# ESP32V1_based_led_button.net
KiCad netlist of a schematic drawn in EAGLE
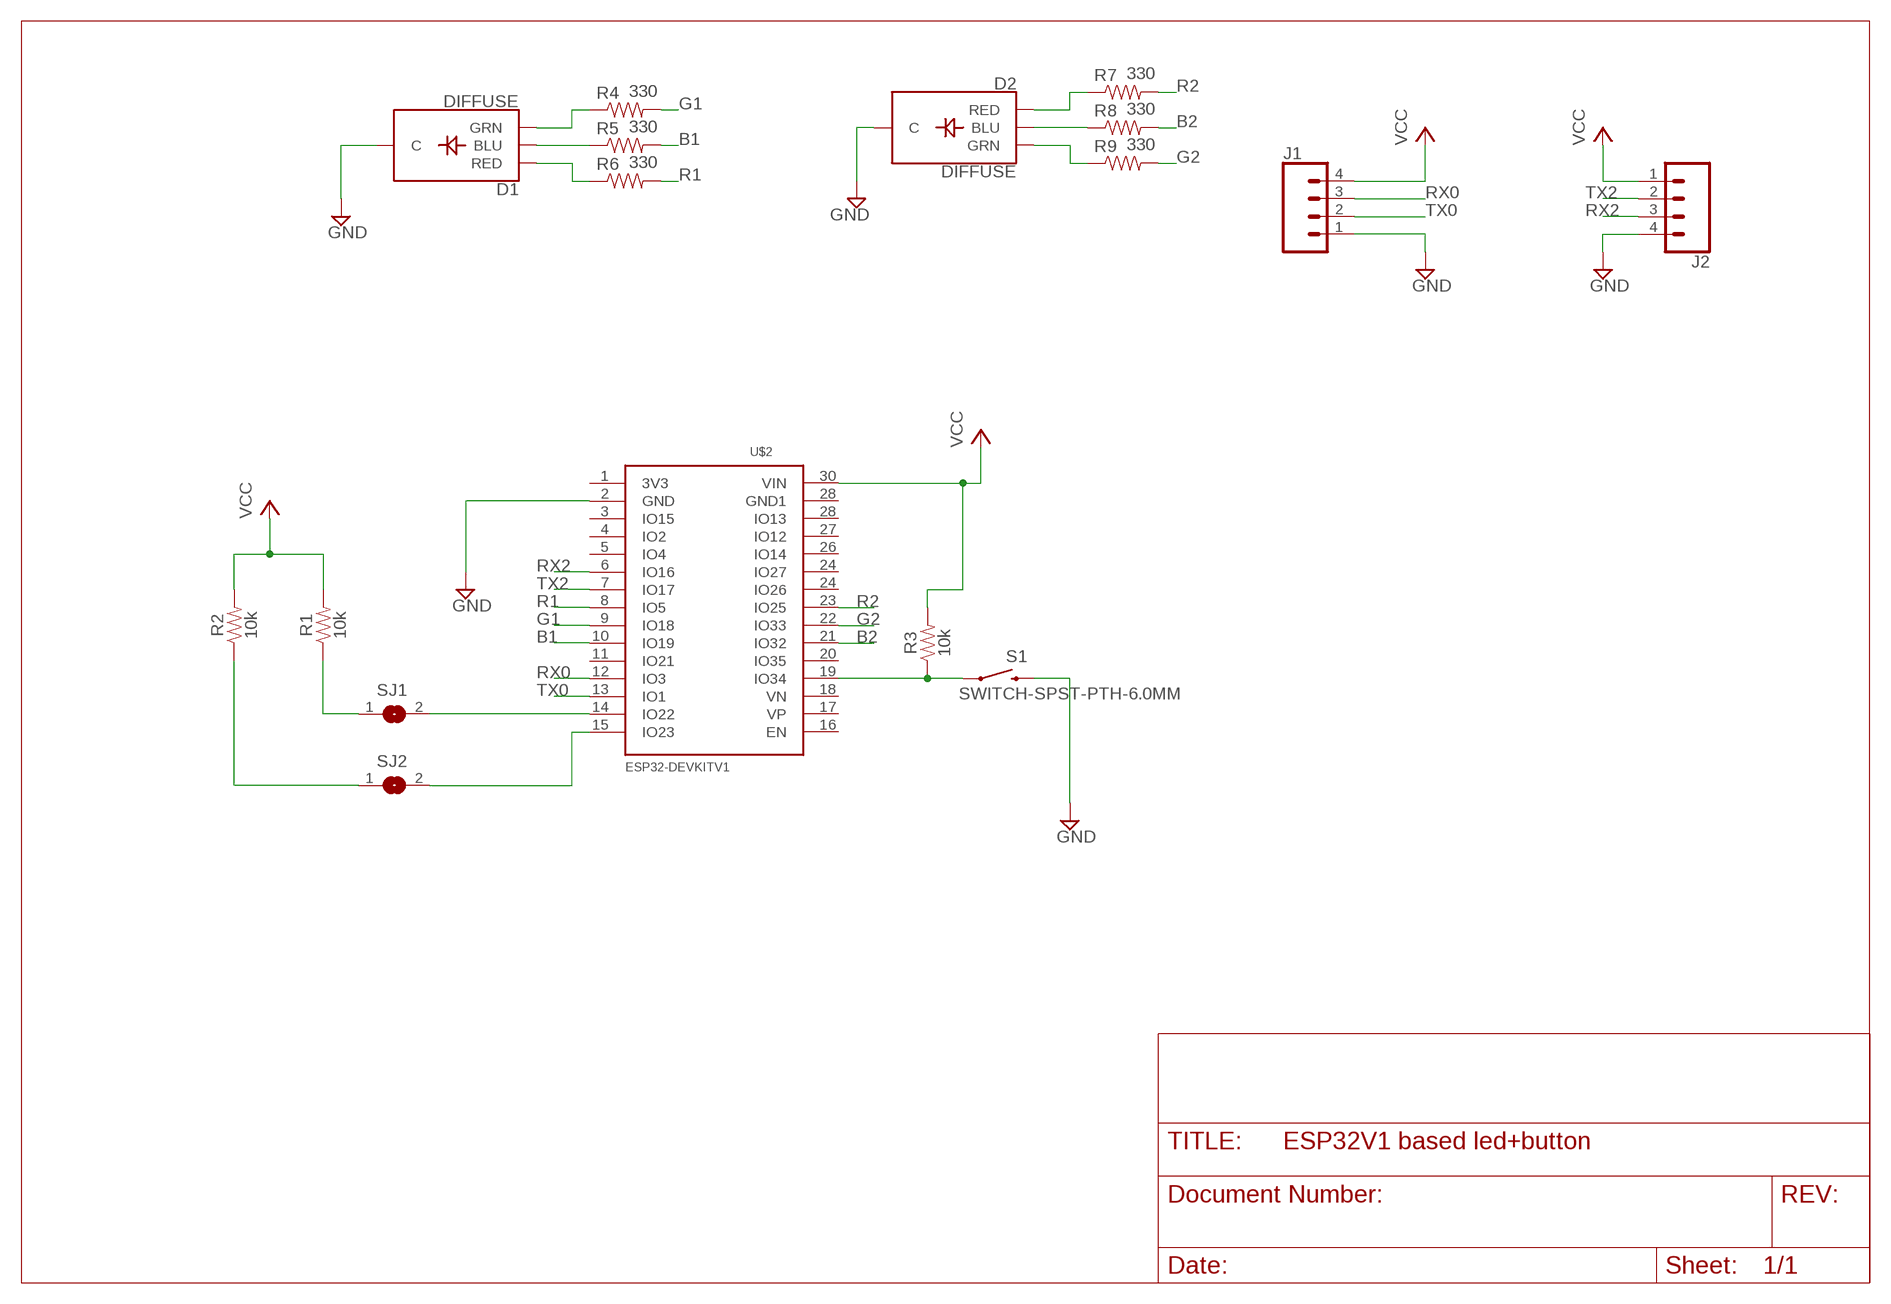
[diagram p0: schematic, sheet 1]

(export (version "E")
  (design (tool "Eeschema 10.0.6"))
  (components
    (comp (ref "D1")
      (value "DIFFUSE")
      (footprint "eagle-import:LED-RGB-THRU")
      (libsource (lib "eagle-import") (part "LED-RGB-CCDIFFUSE"))
    )
    (comp (ref "D2")
      (value "DIFFUSE")
      (footprint "eagle-import:LED-RGB-THRU")
      (libsource (lib "eagle-import") (part "LED-RGB-CCDIFFUSE"))
    )
    (comp (ref "J1")
      (value "CONN_04")
      (footprint "eagle-import:1X04")
      (libsource (lib "eagle-import") (part "CONN_04"))
    )
    (comp (ref "J2")
      (value "CONN_04")
      (footprint "eagle-import:1X04")
      (libsource (lib "eagle-import") (part "CONN_04"))
    )
    (comp (ref "R1")
      (value "10k")
      (footprint "eagle-import:AXIAL-0.3")
      (libsource (lib "eagle-import") (part "10KOHM-HORIZ-1/4W-1%"))
    )
    (comp (ref "R2")
      (value "10k")
      (footprint "eagle-import:AXIAL-0.3")
      (libsource (lib "eagle-import") (part "10KOHM-HORIZ-1/4W-1%"))
    )
    (comp (ref "R3")
      (value "10k")
      (footprint "eagle-import:AXIAL-0.3")
      (libsource (lib "eagle-import") (part "10KOHM-HORIZ-1/4W-1%"))
    )
    (comp (ref "R4")
      (value "330")
      (footprint "eagle-import:AXIAL-0.3")
      (libsource (lib "eagle-import") (part "330OHM-HORIZ-1/10W-5%"))
    )
    (comp (ref "R5")
      (value "330")
      (footprint "eagle-import:AXIAL-0.3")
      (libsource (lib "eagle-import") (part "330OHM-HORIZ-1/10W-5%"))
    )
    (comp (ref "R6")
      (value "330")
      (footprint "eagle-import:AXIAL-0.3")
      (libsource (lib "eagle-import") (part "330OHM-HORIZ-1/10W-5%"))
    )
    (comp (ref "R7")
      (value "330")
      (footprint "eagle-import:AXIAL-0.3")
      (libsource (lib "eagle-import") (part "330OHM-HORIZ-1/10W-5%"))
    )
    (comp (ref "R8")
      (value "330")
      (footprint "eagle-import:AXIAL-0.3")
      (libsource (lib "eagle-import") (part "330OHM-HORIZ-1/10W-5%"))
    )
    (comp (ref "R9")
      (value "330")
      (footprint "eagle-import:AXIAL-0.3")
      (libsource (lib "eagle-import") (part "330OHM-HORIZ-1/10W-5%"))
    )
    (comp (ref "S1")
      (value "SWITCH-SPST-PTH-6.0MM")
      (footprint "eagle-import:TACTILE_SWITCH_PTH_6.0MM_KIT")
      (libsource (lib "eagle-import") (part "MOMENTARY-SWITCH-SPST-PTH-6.0MM-KIT"))
    )
    (comp (ref "SJ1")
      (value "SJW")
      (footprint "eagle-import:SJW")
      (libsource (lib "eagle-import") (part "SJW"))
    )
    (comp (ref "SJ2")
      (value "SJW")
      (footprint "eagle-import:SJW")
      (libsource (lib "eagle-import") (part "SJW"))
    )
    (comp (ref "U$2")
      (value "ESP32DEVKITV1")
      (footprint "eagle-import:ESP32-DEVKITV1")
      (libsource (lib "eagle-import") (part "ESP32DEVKITV1"))
    )
  )
  (nets
    (net (code "1") (name "/B1") (class "Default")
      (node (ref "R5") (pin "P$2") (pinfunction "2_P$2") (pintype "passive"))
      (node (ref "U$2") (pin "10") (pinfunction "IO19_10") (pintype "bidirectional"))
    )
    (net (code "2") (name "/B2") (class "Default")
      (node (ref "R8") (pin "P$2") (pinfunction "2_P$2") (pintype "passive"))
      (node (ref "U$2") (pin "21") (pinfunction "IO32_21") (pintype "bidirectional"))
    )
    (net (code "3") (name "/G1") (class "Default")
      (node (ref "R4") (pin "P$2") (pinfunction "2_P$2") (pintype "passive"))
      (node (ref "U$2") (pin "9") (pinfunction "IO18_9") (pintype "bidirectional"))
    )
    (net (code "4") (name "/G2") (class "Default")
      (node (ref "R9") (pin "P$2") (pinfunction "2_P$2") (pintype "passive"))
      (node (ref "U$2") (pin "22") (pinfunction "IO33_22") (pintype "bidirectional"))
    )
    (net (code "5") (name "/R1") (class "Default")
      (node (ref "R6") (pin "P$2") (pinfunction "2_P$2") (pintype "passive"))
      (node (ref "U$2") (pin "8") (pinfunction "IO5_8") (pintype "bidirectional"))
    )
    (net (code "6") (name "/R2") (class "Default")
      (node (ref "R7") (pin "P$2") (pinfunction "2_P$2") (pintype "passive"))
      (node (ref "U$2") (pin "23") (pinfunction "IO25_23") (pintype "bidirectional"))
    )
    (net (code "7") (name "/RX0") (class "Default")
      (node (ref "J1") (pin "3") (pinfunction "3_3") (pintype "passive"))
      (node (ref "U$2") (pin "12") (pinfunction "IO3_12") (pintype "bidirectional"))
    )
    (net (code "8") (name "/RX2") (class "Default")
      (node (ref "J2") (pin "3") (pinfunction "3_3") (pintype "passive"))
      (node (ref "U$2") (pin "6") (pinfunction "IO16_6") (pintype "bidirectional"))
    )
    (net (code "9") (name "/TX0") (class "Default")
      (node (ref "J1") (pin "2") (pinfunction "2_2") (pintype "passive"))
      (node (ref "U$2") (pin "13") (pinfunction "IO1_13") (pintype "bidirectional"))
    )
    (net (code "10") (name "/TX2") (class "Default")
      (node (ref "J2") (pin "2") (pinfunction "2_2") (pintype "passive"))
      (node (ref "U$2") (pin "7") (pinfunction "IO17_7") (pintype "bidirectional"))
    )
    (net (code "11") (name "GND") (class "Default")
      (node (ref "D1") (pin "2") (pinfunction "C_2") (pintype "bidirectional"))
      (node (ref "D2") (pin "2") (pinfunction "C_2") (pintype "bidirectional"))
      (node (ref "J1") (pin "1") (pinfunction "1_1") (pintype "passive"))
      (node (ref "J2") (pin "4") (pinfunction "4_4") (pintype "passive"))
      (node (ref "S1") (pin "3") (pinfunction "2_3") (pintype "passive"))
      (node (ref "U$2") (pin "2") (pinfunction "GND_2") (pintype "bidirectional"))
    )
    (net (code "12") (name "Net-(D1-BLU)") (class "Default")
      (node (ref "D1") (pin "4") (pinfunction "BLU_4") (pintype "bidirectional"))
      (node (ref "R5") (pin "P$1") (pinfunction "1_P$1") (pintype "passive"))
    )
    (net (code "13") (name "Net-(D1-GRN)") (class "Default")
      (node (ref "D1") (pin "3") (pinfunction "GRN_3") (pintype "bidirectional"))
      (node (ref "R4") (pin "P$1") (pinfunction "1_P$1") (pintype "passive"))
    )
    (net (code "14") (name "Net-(D1-RED)") (class "Default")
      (node (ref "D1") (pin "1") (pinfunction "RED_1") (pintype "bidirectional"))
      (node (ref "R6") (pin "P$1") (pinfunction "1_P$1") (pintype "passive"))
    )
    (net (code "15") (name "Net-(D2-BLU)") (class "Default")
      (node (ref "D2") (pin "4") (pinfunction "BLU_4") (pintype "bidirectional"))
      (node (ref "R8") (pin "P$1") (pinfunction "1_P$1") (pintype "passive"))
    )
    (net (code "16") (name "Net-(D2-GRN)") (class "Default")
      (node (ref "D2") (pin "3") (pinfunction "GRN_3") (pintype "bidirectional"))
      (node (ref "R9") (pin "P$1") (pinfunction "1_P$1") (pintype "passive"))
    )
    (net (code "17") (name "Net-(D2-RED)") (class "Default")
      (node (ref "D2") (pin "1") (pinfunction "RED_1") (pintype "bidirectional"))
      (node (ref "R7") (pin "P$1") (pinfunction "1_P$1") (pintype "passive"))
    )
    (net (code "18") (name "Net-(R1-1)") (class "Default")
      (node (ref "R1") (pin "P$1") (pinfunction "1_P$1") (pintype "passive"))
      (node (ref "SJ1") (pin "1") (pinfunction "1_1") (pintype "passive"))
    )
    (net (code "19") (name "Net-(R2-1)") (class "Default")
      (node (ref "R2") (pin "P$1") (pinfunction "1_P$1") (pintype "passive"))
      (node (ref "SJ2") (pin "1") (pinfunction "1_1") (pintype "passive"))
    )
    (net (code "20") (name "Net-(R3-1)") (class "Default")
      (node (ref "R3") (pin "P$1") (pinfunction "1_P$1") (pintype "passive"))
      (node (ref "S1") (pin "1") (pinfunction "1_1") (pintype "passive"))
      (node (ref "U$2") (pin "19") (pinfunction "IO34_19") (pintype "bidirectional"))
    )
    (net (code "21") (name "Net-(U$2-IO22)") (class "Default")
      (node (ref "SJ1") (pin "2") (pinfunction "2_2") (pintype "passive"))
      (node (ref "U$2") (pin "14") (pinfunction "IO22_14") (pintype "bidirectional"))
    )
    (net (code "22") (name "Net-(U$2-IO23)") (class "Default")
      (node (ref "SJ2") (pin "2") (pinfunction "2_2") (pintype "passive"))
      (node (ref "U$2") (pin "15") (pinfunction "IO23_15") (pintype "bidirectional"))
    )
    (net (code "23") (name "VCC") (class "Default")
      (node (ref "J1") (pin "4") (pinfunction "4_4") (pintype "passive"))
      (node (ref "J2") (pin "1") (pinfunction "1_1") (pintype "passive"))
      (node (ref "R1") (pin "P$2") (pinfunction "2_P$2") (pintype "passive"))
      (node (ref "R2") (pin "P$2") (pinfunction "2_P$2") (pintype "passive"))
      (node (ref "R3") (pin "P$2") (pinfunction "2_P$2") (pintype "passive"))
      (node (ref "U$2") (pin "30") (pinfunction "VIN_30") (pintype "bidirectional"))
    )
    (net (code "24") (name "unconnected-(U$2-3V3-Pad1)") (class "Default")
      (node (ref "U$2") (pin "1") (pinfunction "3V3_1") (pintype "bidirectional"))
    )
    (net (code "25") (name "unconnected-(U$2-EN-Pad16)") (class "Default")
      (node (ref "U$2") (pin "16") (pinfunction "EN_16") (pintype "bidirectional"))
    )
    (net (code "26") (name "unconnected-(U$2-GND1-Pad28)") (class "Default")
      (node (ref "U$2") (pin "28") (pinfunction "GND1_28") (pintype "bidirectional"))
    )
    (net (code "27") (name "unconnected-(U$2-IO2-Pad4)") (class "Default")
      (node (ref "U$2") (pin "4") (pinfunction "IO2_4") (pintype "bidirectional"))
    )
    (net (code "28") (name "unconnected-(U$2-IO4-Pad5)") (class "Default")
      (node (ref "U$2") (pin "5") (pinfunction "IO4_5") (pintype "bidirectional"))
    )
    (net (code "29") (name "unconnected-(U$2-IO12-Pad27)") (class "Default")
      (node (ref "U$2") (pin "27") (pinfunction "IO12_27") (pintype "bidirectional"))
    )
    (net (code "30") (name "unconnected-(U$2-IO13-Pad28)") (class "Default")
      (node (ref "U$2") (pin "28") (pinfunction "IO13_28") (pintype "bidirectional"))
    )
    (net (code "31") (name "unconnected-(U$2-IO14-Pad26)") (class "Default")
      (node (ref "U$2") (pin "26") (pinfunction "IO14_26") (pintype "bidirectional"))
    )
    (net (code "32") (name "unconnected-(U$2-IO15-Pad3)") (class "Default")
      (node (ref "U$2") (pin "3") (pinfunction "IO15_3") (pintype "bidirectional"))
    )
    (net (code "33") (name "unconnected-(U$2-IO21-Pad11)") (class "Default")
      (node (ref "U$2") (pin "11") (pinfunction "IO21_11") (pintype "bidirectional"))
    )
    (net (code "34") (name "unconnected-(U$2-IO26-Pad24)") (class "Default")
      (node (ref "U$2") (pin "24") (pinfunction "IO26_24") (pintype "bidirectional"))
    )
    (net (code "35") (name "unconnected-(U$2-IO27-Pad24)") (class "Default")
      (node (ref "U$2") (pin "24") (pinfunction "IO27_24") (pintype "bidirectional"))
    )
    (net (code "36") (name "unconnected-(U$2-IO35-Pad20)") (class "Default")
      (node (ref "U$2") (pin "20") (pinfunction "IO35_20") (pintype "bidirectional"))
    )
    (net (code "37") (name "unconnected-(U$2-VN-Pad18)") (class "Default")
      (node (ref "U$2") (pin "18") (pinfunction "VN_18") (pintype "bidirectional"))
    )
    (net (code "38") (name "unconnected-(U$2-VP-Pad17)") (class "Default")
      (node (ref "U$2") (pin "17") (pinfunction "VP_17") (pintype "bidirectional"))
    )
  )
)
